# NextOne.net
KiCad netlist of a schematic drawn in EAGLE
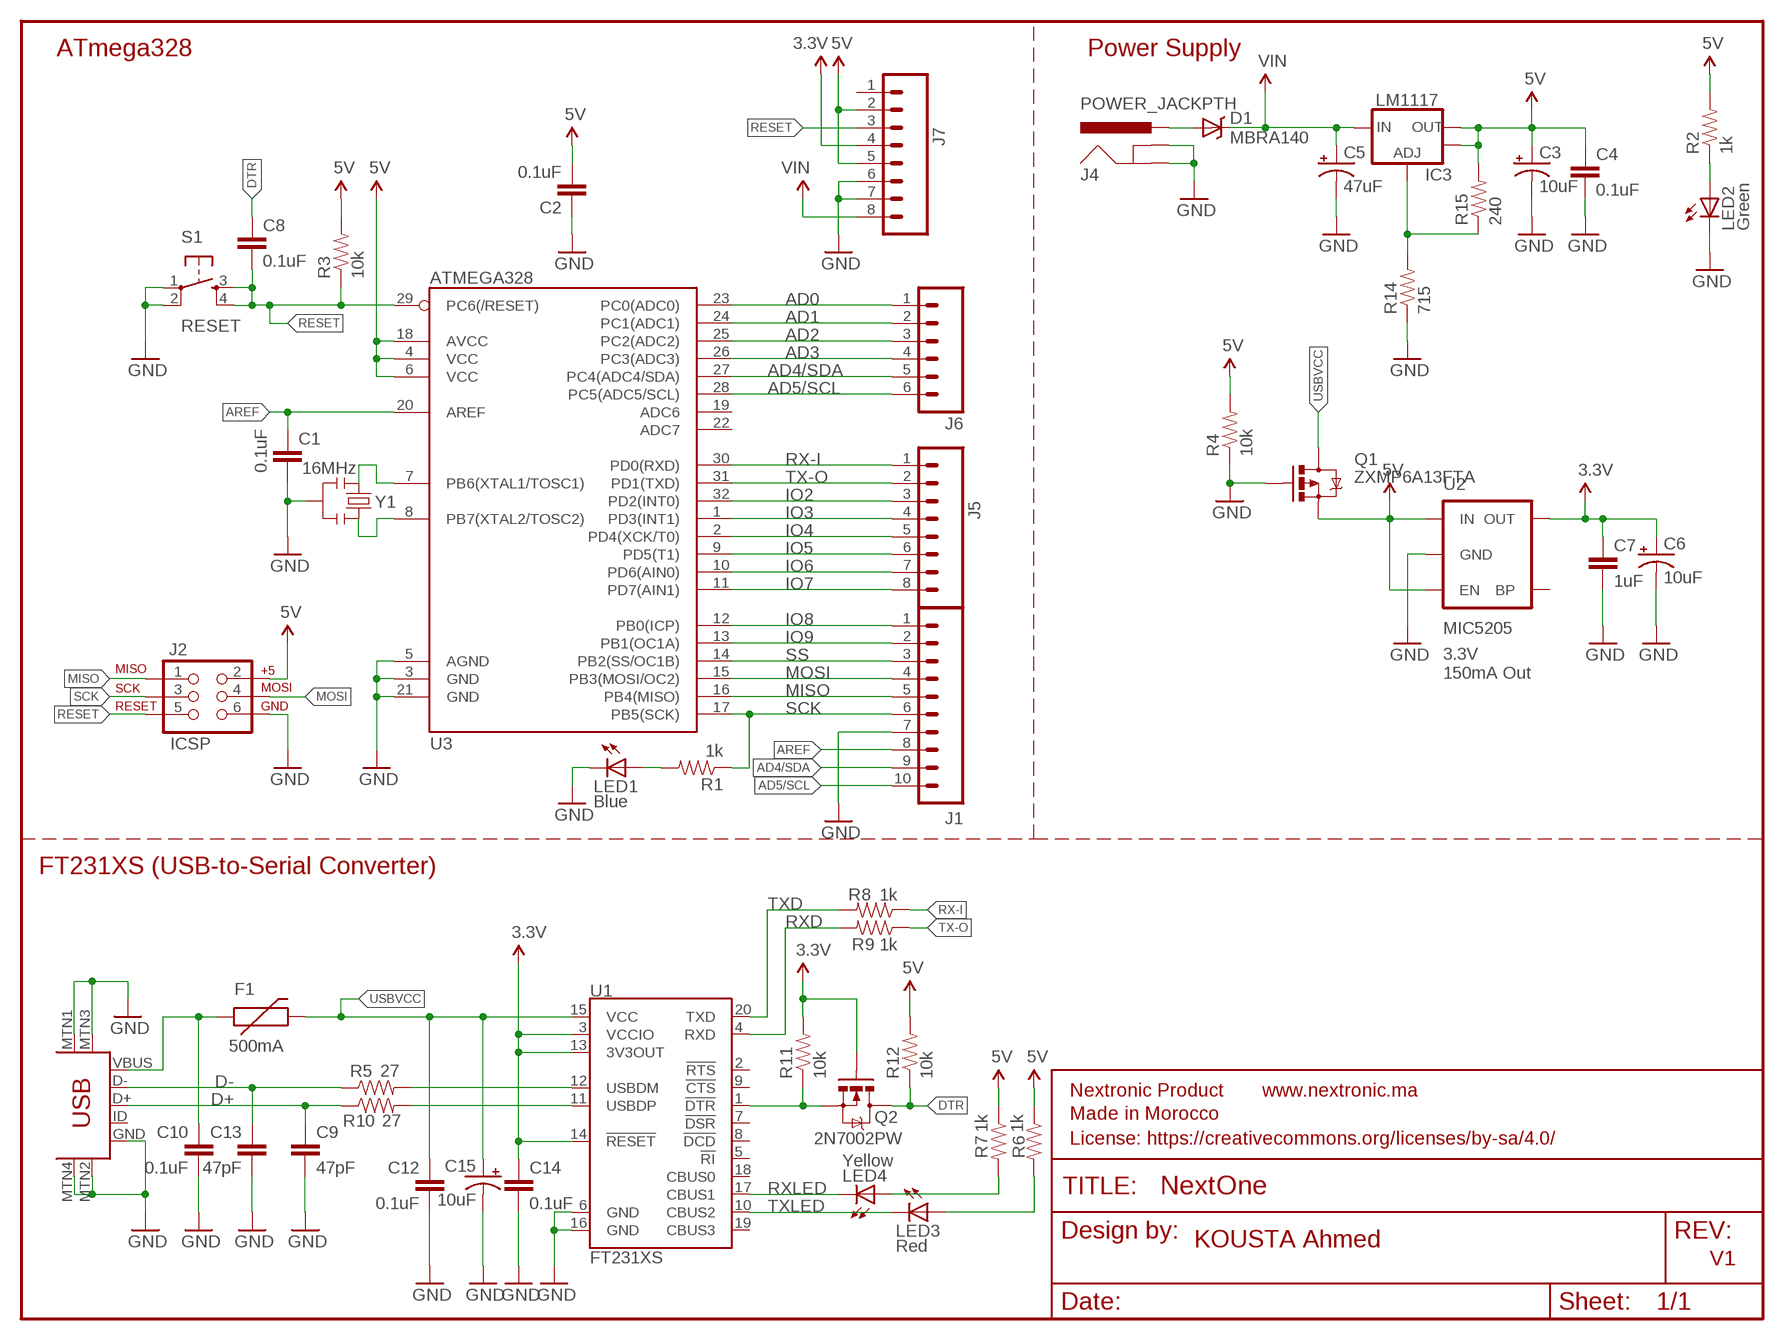
[diagram p0: schematic, sheet 1]

(export (version "E")
  (design (tool "Eeschema 10.0.6"))
  (components
    (comp (ref "C1")
      (value "0.1uF")
      (footprint "eagle-import:0603-CAP")
      (libsource (lib "eagle-import") (part "CAP0603-CAP"))
    )
    (comp (ref "C2")
      (value "0.1uF")
      (footprint "eagle-import:0603-CAP")
      (libsource (lib "eagle-import") (part "CAP0603-CAP"))
    )
    (comp (ref "C3")
      (value "10uF")
      (footprint "eagle-import:EIA3216")
      (libsource (lib "eagle-import") (part "CAP_POL1206"))
    )
    (comp (ref "C4")
      (value "0.1uF")
      (footprint "eagle-import:0603-CAP")
      (libsource (lib "eagle-import") (part "CAP0603-CAP"))
    )
    (comp (ref "C5")
      (value "47uF")
      (footprint "eagle-import:PANASONIC_D")
      (fields (field (name "MF") "PANASONIC ELECTRONIC COMPONENTS") (field (name "MPN") "EEE1CA470SP"))
      (libsource (lib "eagle-import") (part "CAP_POLD"))
    )
    (comp (ref "C6")
      (value "10uF")
      (footprint "eagle-import:EIA3216")
      (libsource (lib "eagle-import") (part "CAP_POL1206"))
    )
    (comp (ref "C7")
      (value "1uF")
      (footprint "eagle-import:0603-CAP")
      (fields (field (name "MF") "WALSIN") (field (name "MPN") "0805B104K500CT"))
      (libsource (lib "eagle-import") (part "CAP0603-CAP"))
    )
    (comp (ref "C8")
      (value "0.1uF")
      (footprint "eagle-import:0603-CAP")
      (libsource (lib "eagle-import") (part "CAP0603-CAP"))
    )
    (comp (ref "C9")
      (value "47pF")
      (footprint "eagle-import:0603-CAP")
      (fields (field (name "MF") "AVX") (field (name "MPN") "12061A470JAT2A"))
      (libsource (lib "eagle-import") (part "47PF-50V-5%(0603)"))
    )
    (comp (ref "C10")
      (value "0.1uF")
      (footprint "eagle-import:0603-CAP")
      (libsource (lib "eagle-import") (part "CAP0603-CAP"))
    )
    (comp (ref "C12")
      (value "0.1uF")
      (footprint "eagle-import:0603-CAP")
      (libsource (lib "eagle-import") (part "CAP0603-CAP"))
    )
    (comp (ref "C13")
      (value "47pF")
      (footprint "eagle-import:0603-CAP")
      (fields (field (name "MF") "AVX") (field (name "MPN") "12061A470JAT2A"))
      (libsource (lib "eagle-import") (part "47PF-50V-5%(0603)"))
    )
    (comp (ref "C14")
      (value "0.1uF")
      (footprint "eagle-import:0603-CAP")
      (libsource (lib "eagle-import") (part "CAP0603-CAP"))
    )
    (comp (ref "C15")
      (value "10uF")
      (footprint "eagle-import:EIA3216")
      (libsource (lib "eagle-import") (part "SparkFun-Capacitors_CAP_POL1206"))
    )
    (comp (ref "D1")
      (value "MBRA140")
      (footprint "eagle-import:SMA-DIODE")
      (fields (field (name "MF") "DIODES INC.") (field (name "MPN") "B140-13-F"))
      (libsource (lib "eagle-import") (part "DIODE-SCHOTTKY_"))
    )
    (comp (ref "F1")
      (value "500mA")
      (footprint "eagle-import:PTC-1206")
      (fields (field (name "MF") "FAIRCHILD SEMICONDUCTOR") (field (name "MPN") "1N3070TR"))
      (libsource (lib "eagle-import") (part "PTCSMD"))
    )
    (comp (ref "FRAME1")
      (value "FRAME-LETTER")
      (footprint "eagle-import:CREATIVE_COMMONS")
      (fields (field (name "OC_FARNELL") "unknown"))
      (libsource (lib "eagle-import") (part "FRAME-LETTER"))
    )
    (comp (ref "IC3")
      (value "LM1117")
      (footprint "eagle-import:SOT223-ALT1")
      (fields (field (name "MF") "STMICROELECTRONICS") (field (name "MPN") "LD1117S33TR"))
      (libsource (lib "eagle-import") (part "V_REG_LM1117ALT1"))
    )
    (comp (ref "J1")
      (value "M10SILK_FEMALE_PTH")
      (footprint "eagle-import:1X10")
      (libsource (lib "eagle-import") (part "M10SILK_FEMALE_PTH"))
    )
    (comp (ref "J2")
      (value "ICSP")
      (footprint "eagle-import:2X3")
      (libsource (lib "eagle-import") (part "AVR_SPI_PRG_6PTH"))
    )
    (comp (ref "J4")
      (value "POWER_JACKPTH")
      (footprint "eagle-import:POWER_JACK_PTH")
      (libsource (lib "eagle-import") (part "POWER_JACKPTH"))
    )
    (comp (ref "J5")
      (value "M08")
      (footprint "eagle-import:1X08_ROUND")
      (libsource (lib "eagle-import") (part "M08"))
    )
    (comp (ref "J6")
      (value "M06SILK_FEMALE_PTH")
      (footprint "eagle-import:1X06")
      (libsource (lib "eagle-import") (part "M06SILK_FEMALE_PTH"))
    )
    (comp (ref "J7")
      (value "M08")
      (footprint "eagle-import:1X08_ROUND")
      (libsource (lib "eagle-import") (part "M08"))
    )
    (comp (ref "LED1")
      (value "Blue")
      (footprint "eagle-import:LED-1206-NO_SILK")
      (libsource (lib "eagle-import") (part "LED1206-NS"))
    )
    (comp (ref "LED2")
      (value "Green")
      (footprint "eagle-import:LED-1206-NO_SILK")
      (libsource (lib "eagle-import") (part "LED1206-NS"))
    )
    (comp (ref "LED3")
      (value "Red")
      (footprint "eagle-import:LED-1206-NO_SILK")
      (libsource (lib "eagle-import") (part "LED1206-NS"))
    )
    (comp (ref "LED4")
      (value "Yellow")
      (footprint "eagle-import:LED-1206-NO_SILK")
      (libsource (lib "eagle-import") (part "LED1206-NS"))
    )
    (comp (ref "Q1")
      (value "ZXMP6A13FTA")
      (footprint "eagle-import:SOT23-3")
      (fields (field (name "MF") "DIODES INC."))
      (libsource (lib "eagle-import") (part "MOSFET-PCHANNELSMD"))
    )
    (comp (ref "Q2")
      (value "2N7002PW")
      (footprint "eagle-import:SOT323")
      (libsource (lib "eagle-import") (part "MOSFET-NCHANNEL2N7002PW"))
    )
    (comp (ref "R1")
      (value "1k")
      (footprint "eagle-import:0603-RES")
      (libsource (lib "eagle-import") (part "RESISTOR0603-RES"))
    )
    (comp (ref "R2")
      (value "1k")
      (footprint "eagle-import:0603-RES")
      (libsource (lib "eagle-import") (part "RESISTOR0603-RES"))
    )
    (comp (ref "R3")
      (value "10k")
      (footprint "eagle-import:0603-RES")
      (libsource (lib "eagle-import") (part "RESISTOR0603-RES"))
    )
    (comp (ref "R4")
      (value "10k")
      (footprint "eagle-import:0603-RES")
      (libsource (lib "eagle-import") (part "RESISTOR0603-RES"))
    )
    (comp (ref "R5")
      (value "27")
      (footprint "eagle-import:0603-RES")
      (libsource (lib "eagle-import") (part "SparkFun-Resistors_RESISTOR0603-RES"))
    )
    (comp (ref "R6")
      (value "1k")
      (footprint "eagle-import:0603-RES")
      (libsource (lib "eagle-import") (part "RESISTOR0603-RES"))
    )
    (comp (ref "R7")
      (value "1k")
      (footprint "eagle-import:0603-RES")
      (libsource (lib "eagle-import") (part "RESISTOR0603-RES"))
    )
    (comp (ref "R8")
      (value "1k")
      (footprint "eagle-import:0603-RES")
      (libsource (lib "eagle-import") (part "RESISTOR0603-RES"))
    )
    (comp (ref "R9")
      (value "1k")
      (footprint "eagle-import:0603-RES")
      (libsource (lib "eagle-import") (part "RESISTOR0603-RES"))
    )
    (comp (ref "R10")
      (value "27")
      (footprint "eagle-import:0603-RES")
      (libsource (lib "eagle-import") (part "SparkFun-Resistors_RESISTOR0603-RES"))
    )
    (comp (ref "R11")
      (value "10k")
      (footprint "eagle-import:0603-RES")
      (libsource (lib "eagle-import") (part "RESISTOR0603-RES"))
    )
    (comp (ref "R12")
      (value "10k")
      (footprint "eagle-import:0603-RES")
      (libsource (lib "eagle-import") (part "RESISTOR0603-RES"))
    )
    (comp (ref "R14")
      (value "715")
      (footprint "eagle-import:0603-RES")
      (libsource (lib "eagle-import") (part "RESISTOR0603-RES"))
    )
    (comp (ref "R15")
      (value "240")
      (footprint "eagle-import:0603-RES")
      (libsource (lib "eagle-import") (part "RESISTOR0603-RES"))
    )
    (comp (ref "S1")
      (value "RESET")
      (footprint "eagle-import:TACTILE_SWITCH_SMD")
      (libsource (lib "eagle-import") (part "TAC_SWITCHSMD"))
    )
    (comp (ref "U$13")
      (value "USB-MINIB-5PIN")
      (footprint "eagle-import:USB-MINIB")
      (fields (field (name "MF") "TE CONNECTIVITY / AMP") (field (name "MPN") "1734035-1."))
      (libsource (lib "eagle-import") (part "USB-MINIB-5PIN"))
    )
    (comp (ref "U1")
      (value "FT231XS")
      (footprint "eagle-import:SSOP20_L")
      (fields (field (name "MF") "FTDI"))
      (libsource (lib "eagle-import") (part "FT231XS"))
    )
    (comp (ref "U2")
      (value "MIC5205")
      (footprint "eagle-import:SOT23-5")
      (libsource (lib "eagle-import") (part "V_REG_LDOSMD"))
    )
    (comp (ref "U3")
      (value "ATMEGA328")
      (footprint "eagle-import:TQFP32-08")
      (fields (field (name "MF") "ATMEL") (field (name "MPN") "ATMEGA328P-AN"))
      (libsource (lib "eagle-import") (part "ATMEGA168"))
    )
    (comp (ref "Y1")
      (value "16MHz")
      (footprint "eagle-import:RESONATOR-SMD")
      (libsource (lib "eagle-import") (part "RESONATORSMD"))
    )
  )
  (nets
    (net (code "1") (name "/AD0") (class "Default")
      (node (ref "J6") (pin "1") (pinfunction "1_1") (pintype "passive"))
      (node (ref "U3") (pin "23") (pinfunction "PC0(ADC0)_23") (pintype "bidirectional"))
    )
    (net (code "2") (name "/AD1") (class "Default")
      (node (ref "J6") (pin "2") (pinfunction "2_2") (pintype "passive"))
      (node (ref "U3") (pin "24") (pinfunction "PC1(ADC1)_24") (pintype "bidirectional"))
    )
    (net (code "3") (name "/AD2") (class "Default")
      (node (ref "J6") (pin "3") (pinfunction "3_3") (pintype "passive"))
      (node (ref "U3") (pin "25") (pinfunction "PC2(ADC2)_25") (pintype "bidirectional"))
    )
    (net (code "4") (name "/AD3") (class "Default")
      (node (ref "J6") (pin "4") (pinfunction "4_4") (pintype "passive"))
      (node (ref "U3") (pin "26") (pinfunction "PC3(ADC3)_26") (pintype "bidirectional"))
    )
    (net (code "5") (name "/D+") (class "Default")
      (node (ref "C9") (pin "1") (pinfunction "1_1") (pintype "passive"))
      (node (ref "R10") (pin "1") (pinfunction "1_1") (pintype "passive"))
      (node (ref "U$13") (pin "D+") (pinfunction "D+_D+") (pintype "bidirectional"))
    )
    (net (code "6") (name "/D-") (class "Default")
      (node (ref "C13") (pin "1") (pinfunction "1_1") (pintype "passive"))
      (node (ref "R5") (pin "1") (pinfunction "1_1") (pintype "passive"))
      (node (ref "U$13") (pin "D-") (pinfunction "D-_D-") (pintype "bidirectional"))
    )
    (net (code "7") (name "/IO2") (class "Default")
      (node (ref "J5") (pin "3") (pinfunction "3_3") (pintype "passive"))
      (node (ref "U3") (pin "32") (pinfunction "PD2(INT0)_32") (pintype "bidirectional"))
    )
    (net (code "8") (name "/IO3") (class "Default")
      (node (ref "J5") (pin "4") (pinfunction "4_4") (pintype "passive"))
      (node (ref "U3") (pin "1") (pinfunction "PD3(INT1)_1") (pintype "bidirectional"))
    )
    (net (code "9") (name "/IO4") (class "Default")
      (node (ref "J5") (pin "5") (pinfunction "5_5") (pintype "passive"))
      (node (ref "U3") (pin "2") (pinfunction "PD4(XCK/T0)_2") (pintype "bidirectional"))
    )
    (net (code "10") (name "/IO5") (class "Default")
      (node (ref "J5") (pin "6") (pinfunction "6_6") (pintype "passive"))
      (node (ref "U3") (pin "9") (pinfunction "PD5(T1)_9") (pintype "bidirectional"))
    )
    (net (code "11") (name "/IO6") (class "Default")
      (node (ref "J5") (pin "7") (pinfunction "7_7") (pintype "passive"))
      (node (ref "U3") (pin "10") (pinfunction "PD6(AIN0)_10") (pintype "bidirectional"))
    )
    (net (code "12") (name "/IO7") (class "Default")
      (node (ref "J5") (pin "8") (pinfunction "8_8") (pintype "passive"))
      (node (ref "U3") (pin "11") (pinfunction "PD7(AIN1)_11") (pintype "bidirectional"))
    )
    (net (code "13") (name "/IO8") (class "Default")
      (node (ref "J1") (pin "1") (pinfunction "1_1") (pintype "passive"))
      (node (ref "U3") (pin "12") (pinfunction "PB0(ICP)_12") (pintype "bidirectional"))
    )
    (net (code "14") (name "/IO9") (class "Default")
      (node (ref "J1") (pin "2") (pinfunction "2_2") (pintype "passive"))
      (node (ref "U3") (pin "13") (pinfunction "PB1(OC1A)_13") (pintype "bidirectional"))
    )
    (net (code "15") (name "/RXD") (class "Default")
      (node (ref "R9") (pin "2") (pinfunction "2_2") (pintype "passive"))
      (node (ref "U1") (pin "4") (pinfunction "RXD_4") (pintype "bidirectional"))
    )
    (net (code "16") (name "/RXLED") (class "Default")
      (node (ref "LED4") (pin "C") (pinfunction "C_C") (pintype "passive"))
      (node (ref "U1") (pin "17") (pinfunction "CBUS1_17") (pintype "bidirectional"))
    )
    (net (code "17") (name "/SS") (class "Default")
      (node (ref "J1") (pin "3") (pinfunction "3_3") (pintype "passive"))
      (node (ref "U3") (pin "14") (pinfunction "PB2(SS/OC1B)_14") (pintype "bidirectional"))
    )
    (net (code "18") (name "/TXD") (class "Default")
      (node (ref "R8") (pin "2") (pinfunction "2_2") (pintype "passive"))
      (node (ref "U1") (pin "20") (pinfunction "TXD_20") (pintype "bidirectional"))
    )
    (net (code "19") (name "/TXLED") (class "Default")
      (node (ref "LED3") (pin "C") (pinfunction "C_C") (pintype "passive"))
      (node (ref "U1") (pin "10") (pinfunction "CBUS2_10") (pintype "bidirectional"))
    )
    (net (code "20") (name "3.3V") (class "Default")
      (node (ref "C14") (pin "1") (pinfunction "1_1") (pintype "passive"))
      (node (ref "C6") (pin "A") (pinfunction "+_A") (pintype "passive"))
      (node (ref "C7") (pin "1") (pinfunction "1_1") (pintype "passive"))
      (node (ref "J7") (pin "4") (pinfunction "4_4") (pintype "passive"))
      (node (ref "Q2") (pin "1") (pinfunction "G_1") (pintype "passive"))
      (node (ref "R11") (pin "2") (pinfunction "2_2") (pintype "passive"))
      (node (ref "U1") (pin "13") (pinfunction "3V3OUT_13") (pintype "bidirectional"))
      (node (ref "U1") (pin "14") (pinfunction "~{RESET}_14") (pintype "bidirectional"))
      (node (ref "U1") (pin "3") (pinfunction "VCCIO_3") (pintype "bidirectional"))
      (node (ref "U2") (pin "5") (pinfunction "OUT_5") (pintype "passive"))
    )
    (net (code "21") (name "5V") (class "Default")
      (node (ref "C2") (pin "2") (pinfunction "2_2") (pintype "passive"))
      (node (ref "C3") (pin "A") (pinfunction "+_A") (pintype "passive"))
      (node (ref "C4") (pin "1") (pinfunction "1_1") (pintype "passive"))
      (node (ref "IC3") (pin "2") (pinfunction "OUT_2") (pintype "output"))
      (node (ref "IC3") (pin "4") (pinfunction "OUT_4") (pintype "output"))
      (node (ref "J2") (pin "2") (pinfunction "2_2") (pintype "passive"))
      (node (ref "J7") (pin "2") (pinfunction "2_2") (pintype "passive"))
      (node (ref "J7") (pin "5") (pinfunction "5_5") (pintype "passive"))
      (node (ref "Q1") (pin "2") (pinfunction "S_2") (pintype "passive"))
      (node (ref "R12") (pin "2") (pinfunction "2_2") (pintype "passive"))
      (node (ref "R15") (pin "2") (pinfunction "2_2") (pintype "passive"))
      (node (ref "R2") (pin "2") (pinfunction "2_2") (pintype "passive"))
      (node (ref "R3") (pin "2") (pinfunction "2_2") (pintype "passive"))
      (node (ref "R4") (pin "2") (pinfunction "2_2") (pintype "passive"))
      (node (ref "R6") (pin "1") (pinfunction "1_1") (pintype "passive"))
      (node (ref "R7") (pin "1") (pinfunction "1_1") (pintype "passive"))
      (node (ref "U2") (pin "1") (pinfunction "IN_1") (pintype "input"))
      (node (ref "U2") (pin "3") (pinfunction "EN_3") (pintype "input"))
      (node (ref "U3") (pin "18") (pinfunction "AVCC_18") (pintype "bidirectional"))
      (node (ref "U3") (pin "4") (pinfunction "VCC_4") (pintype "bidirectional"))
      (node (ref "U3") (pin "6") (pinfunction "VCC_6") (pintype "bidirectional"))
    )
    (net (code "22") (name "AD4{slash}SDA") (class "Default")
      (node (ref "J1") (pin "9") (pinfunction "9_9") (pintype "passive"))
      (node (ref "J6") (pin "5") (pinfunction "5_5") (pintype "passive"))
      (node (ref "U3") (pin "27") (pinfunction "PC4(ADC4/SDA)_27") (pintype "bidirectional"))
    )
    (net (code "23") (name "AD5{slash}SCL") (class "Default")
      (node (ref "J1") (pin "10") (pinfunction "10_10") (pintype "passive"))
      (node (ref "J6") (pin "6") (pinfunction "6_6") (pintype "passive"))
      (node (ref "U3") (pin "28") (pinfunction "PC5(ADC5/SCL)_28") (pintype "bidirectional"))
    )
    (net (code "24") (name "AREF") (class "Default")
      (node (ref "C1") (pin "1") (pinfunction "1_1") (pintype "passive"))
      (node (ref "J1") (pin "8") (pinfunction "8_8") (pintype "passive"))
      (node (ref "U3") (pin "20") (pinfunction "AREF_20") (pintype "bidirectional"))
    )
    (net (code "25") (name "DTR") (class "Default")
      (node (ref "C8") (pin "1") (pinfunction "1_1") (pintype "passive"))
      (node (ref "Q2") (pin "3") (pinfunction "D_3") (pintype "passive"))
      (node (ref "R12") (pin "1") (pinfunction "1_1") (pintype "passive"))
    )
    (net (code "26") (name "GND") (class "Default")
      (node (ref "C1") (pin "2") (pinfunction "2_2") (pintype "passive"))
      (node (ref "C10") (pin "2") (pinfunction "2_2") (pintype "passive"))
      (node (ref "C12") (pin "2") (pinfunction "2_2") (pintype "passive"))
      (node (ref "C13") (pin "2") (pinfunction "2_2") (pintype "passive"))
      (node (ref "C14") (pin "2") (pinfunction "2_2") (pintype "passive"))
      (node (ref "C15") (pin "C") (pinfunction "-_C") (pintype "passive"))
      (node (ref "C2") (pin "1") (pinfunction "1_1") (pintype "passive"))
      (node (ref "C3") (pin "C") (pinfunction "-_C") (pintype "passive"))
      (node (ref "C4") (pin "2") (pinfunction "2_2") (pintype "passive"))
      (node (ref "C5") (pin "-") (pinfunction "-_-") (pintype "passive"))
      (node (ref "C6") (pin "C") (pinfunction "-_C") (pintype "passive"))
      (node (ref "C7") (pin "2") (pinfunction "2_2") (pintype "passive"))
      (node (ref "C9") (pin "2") (pinfunction "2_2") (pintype "passive"))
      (node (ref "J1") (pin "7") (pinfunction "7_7") (pintype "passive"))
      (node (ref "J2") (pin "6") (pinfunction "6_6") (pintype "passive"))
      (node (ref "J4") (pin "GND") (pinfunction "GND_GND") (pintype "bidirectional"))
      (node (ref "J4") (pin "GNDBREAK") (pinfunction "GNDBREAK_GNDBREAK") (pintype "bidirectional"))
      (node (ref "J7") (pin "6") (pinfunction "6_6") (pintype "passive"))
      (node (ref "J7") (pin "7") (pinfunction "7_7") (pintype "passive"))
      (node (ref "LED1") (pin "C") (pinfunction "C_C") (pintype "passive"))
      (node (ref "LED2") (pin "C") (pinfunction "C_C") (pintype "passive"))
      (node (ref "Q1") (pin "1") (pinfunction "G_1") (pintype "passive"))
      (node (ref "R14") (pin "1") (pinfunction "1_1") (pintype "passive"))
      (node (ref "R4") (pin "1") (pinfunction "1_1") (pintype "passive"))
      (node (ref "S1") (pin "1") (pinfunction "1_1") (pintype "passive"))
      (node (ref "S1") (pin "2") (pinfunction "2_2") (pintype "passive"))
      (node (ref "U$13") (pin "GND") (pinfunction "GND_GND") (pintype "bidirectional"))
      (node (ref "U$13") (pin "MTN1") (pinfunction "MTN2_MTN1") (pintype "bidirectional"))
      (node (ref "U$13") (pin "MTN2") (pinfunction "MTN3_MTN2") (pintype "bidirectional"))
      (node (ref "U$13") (pin "MTN3") (pinfunction "MTN1_MTN3") (pintype "bidirectional"))
      (node (ref "U$13") (pin "MTN4") (pinfunction "MTN4_MTN4") (pintype "bidirectional"))
      (node (ref "U1") (pin "16") (pinfunction "GND_16") (pintype "bidirectional"))
      (node (ref "U1") (pin "6") (pinfunction "GND_6") (pintype "bidirectional"))
      (node (ref "U2") (pin "2") (pinfunction "GND_2") (pintype "input"))
      (node (ref "U3") (pin "21") (pinfunction "GND_21") (pintype "bidirectional"))
      (node (ref "U3") (pin "3") (pinfunction "GND_3") (pintype "bidirectional"))
      (node (ref "U3") (pin "5") (pinfunction "AGND_5") (pintype "bidirectional"))
      (node (ref "Y1") (pin "2") (pinfunction "2_2") (pintype "passive"))
    )
    (net (code "27") (name "MISO") (class "Default")
      (node (ref "J1") (pin "5") (pinfunction "5_5") (pintype "passive"))
      (node (ref "J2") (pin "1") (pinfunction "1_1") (pintype "passive"))
      (node (ref "U3") (pin "16") (pinfunction "PB4(MISO)_16") (pintype "bidirectional"))
    )
    (net (code "28") (name "MOSI") (class "Default")
      (node (ref "J1") (pin "4") (pinfunction "4_4") (pintype "passive"))
      (node (ref "J2") (pin "4") (pinfunction "4_4") (pintype "passive"))
      (node (ref "U3") (pin "15") (pinfunction "PB3(MOSI/OC2)_15") (pintype "bidirectional"))
    )
    (net (code "29") (name "Net-(C10-Pad1)") (class "Default")
      (node (ref "C10") (pin "1") (pinfunction "1_1") (pintype "passive"))
      (node (ref "F1") (pin "1") (pinfunction "1_1") (pintype "bidirectional"))
      (node (ref "U$13") (pin "VBUS") (pinfunction "VBUS_VBUS") (pintype "bidirectional"))
    )
    (net (code "30") (name "Net-(D1-PadA)") (class "Default")
      (node (ref "D1") (pin "A") (pinfunction "A_A") (pintype "passive"))
      (node (ref "J4") (pin "PWR") (pinfunction "PWR_PWR") (pintype "bidirectional"))
    )
    (net (code "31") (name "Net-(IC3-ADJ)") (class "Default")
      (node (ref "IC3") (pin "1") (pinfunction "ADJ_1") (pintype "input"))
      (node (ref "R14") (pin "2") (pinfunction "2_2") (pintype "passive"))
      (node (ref "R15") (pin "1") (pinfunction "1_1") (pintype "passive"))
    )
    (net (code "32") (name "Net-(LED1-PadA)") (class "Default")
      (node (ref "LED1") (pin "A") (pinfunction "A_A") (pintype "passive"))
      (node (ref "R1") (pin "2") (pinfunction "2_2") (pintype "passive"))
    )
    (net (code "33") (name "Net-(LED2-PadA)") (class "Default")
      (node (ref "LED2") (pin "A") (pinfunction "A_A") (pintype "passive"))
      (node (ref "R2") (pin "1") (pinfunction "1_1") (pintype "passive"))
    )
    (net (code "34") (name "Net-(LED3-PadA)") (class "Default")
      (node (ref "LED3") (pin "A") (pinfunction "A_A") (pintype "passive"))
      (node (ref "R6") (pin "2") (pinfunction "2_2") (pintype "passive"))
    )
    (net (code "35") (name "Net-(LED4-PadA)") (class "Default")
      (node (ref "LED4") (pin "A") (pinfunction "A_A") (pintype "passive"))
      (node (ref "R7") (pin "2") (pinfunction "2_2") (pintype "passive"))
    )
    (net (code "36") (name "Net-(Q2-S)") (class "Default")
      (node (ref "Q2") (pin "2") (pinfunction "S_2") (pintype "passive"))
      (node (ref "R11") (pin "1") (pinfunction "1_1") (pintype "passive"))
      (node (ref "U1") (pin "1") (pinfunction "~{DTR}_1") (pintype "bidirectional"))
    )
    (net (code "37") (name "Net-(U1-USBDM)") (class "Default")
      (node (ref "R5") (pin "2") (pinfunction "2_2") (pintype "passive"))
      (node (ref "U1") (pin "12") (pinfunction "USBDM_12") (pintype "bidirectional"))
    )
    (net (code "38") (name "Net-(U1-USBDP)") (class "Default")
      (node (ref "R10") (pin "2") (pinfunction "2_2") (pintype "passive"))
      (node (ref "U1") (pin "11") (pinfunction "USBDP_11") (pintype "bidirectional"))
    )
    (net (code "39") (name "Net-(U3-PB6(XTAL1{slash}TOSC1))") (class "Default")
      (node (ref "U3") (pin "7") (pinfunction "PB6(XTAL1/TOSC1)_7") (pintype "bidirectional"))
      (node (ref "Y1") (pin "1") (pinfunction "1_1") (pintype "passive"))
    )
    (net (code "40") (name "Net-(U3-PB7(XTAL2{slash}TOSC2))") (class "Default")
      (node (ref "U3") (pin "8") (pinfunction "PB7(XTAL2/TOSC2)_8") (pintype "bidirectional"))
      (node (ref "Y1") (pin "3") (pinfunction "3_3") (pintype "passive"))
    )
    (net (code "41") (name "RESET") (class "Default")
      (node (ref "C8") (pin "2") (pinfunction "2_2") (pintype "passive"))
      (node (ref "J2") (pin "5") (pinfunction "5_5") (pintype "passive"))
      (node (ref "J7") (pin "3") (pinfunction "3_3") (pintype "passive"))
      (node (ref "R3") (pin "1") (pinfunction "1_1") (pintype "passive"))
      (node (ref "S1") (pin "3") (pinfunction "3_3") (pintype "passive"))
      (node (ref "S1") (pin "4") (pinfunction "4_4") (pintype "passive"))
      (node (ref "U3") (pin "29") (pinfunction "PC6(/RESET)_29") (pintype "bidirectional"))
    )
    (net (code "42") (name "RX-I") (class "Default")
      (node (ref "J5") (pin "1") (pinfunction "1_1") (pintype "passive"))
      (node (ref "R8") (pin "1") (pinfunction "1_1") (pintype "passive"))
      (node (ref "U3") (pin "30") (pinfunction "PD0(RXD)_30") (pintype "bidirectional"))
    )
    (net (code "43") (name "SCK") (class "Default")
      (node (ref "J1") (pin "6") (pinfunction "6_6") (pintype "passive"))
      (node (ref "J2") (pin "3") (pinfunction "3_3") (pintype "passive"))
      (node (ref "R1") (pin "1") (pinfunction "1_1") (pintype "passive"))
      (node (ref "U3") (pin "17") (pinfunction "PB5(SCK)_17") (pintype "bidirectional"))
    )
    (net (code "44") (name "TX-O") (class "Default")
      (node (ref "J5") (pin "2") (pinfunction "2_2") (pintype "passive"))
      (node (ref "R9") (pin "1") (pinfunction "1_1") (pintype "passive"))
      (node (ref "U3") (pin "31") (pinfunction "PD1(TXD)_31") (pintype "bidirectional"))
    )
    (net (code "45") (name "USBVCC") (class "Default")
      (node (ref "C12") (pin "1") (pinfunction "1_1") (pintype "passive"))
      (node (ref "C15") (pin "A") (pinfunction "+_A") (pintype "passive"))
      (node (ref "F1") (pin "2") (pinfunction "2_2") (pintype "bidirectional"))
      (node (ref "Q1") (pin "3") (pinfunction "D_3") (pintype "passive"))
      (node (ref "U1") (pin "15") (pinfunction "VCC_15") (pintype "bidirectional"))
    )
    (net (code "46") (name "VIN") (class "Default")
      (node (ref "C5") (pin "+") (pinfunction "+_+") (pintype "passive"))
      (node (ref "D1") (pin "C") (pinfunction "C_C") (pintype "passive"))
      (node (ref "IC3") (pin "3") (pinfunction "IN_3") (pintype "input"))
      (node (ref "J7") (pin "8") (pinfunction "8_8") (pintype "passive"))
    )
    (net (code "47") (name "unconnected-(J7-Pad1)") (class "Default")
      (node (ref "J7") (pin "1") (pinfunction "1_1") (pintype "passive"))
    )
    (net (code "48") (name "unconnected-(U$13-PadID)") (class "Default")
      (node (ref "U$13") (pin "ID") (pinfunction "ID_ID") (pintype "bidirectional"))
    )
    (net (code "49") (name "unconnected-(U1-CBUS0-Pad18)") (class "Default")
      (node (ref "U1") (pin "18") (pinfunction "CBUS0_18") (pintype "bidirectional"))
    )
    (net (code "50") (name "unconnected-(U1-CBUS3-Pad19)") (class "Default")
      (node (ref "U1") (pin "19") (pinfunction "CBUS3_19") (pintype "bidirectional"))
    )
    (net (code "51") (name "unconnected-(U1-~{CTS}-Pad9)") (class "Default")
      (node (ref "U1") (pin "9") (pinfunction "~{CTS}_9") (pintype "bidirectional"))
    )
    (net (code "52") (name "unconnected-(U1-~{DCD}-Pad8)") (class "Default")
      (node (ref "U1") (pin "8") (pinfunction "~{DCD}_8") (pintype "bidirectional"))
    )
    (net (code "53") (name "unconnected-(U1-~{DSR}-Pad7)") (class "Default")
      (node (ref "U1") (pin "7") (pinfunction "~{DSR}_7") (pintype "bidirectional"))
    )
    (net (code "54") (name "unconnected-(U1-~{RI}-Pad5)") (class "Default")
      (node (ref "U1") (pin "5") (pinfunction "~{RI}_5") (pintype "bidirectional"))
    )
    (net (code "55") (name "unconnected-(U1-~{RTS}-Pad2)") (class "Default")
      (node (ref "U1") (pin "2") (pinfunction "~{RTS}_2") (pintype "bidirectional"))
    )
    (net (code "56") (name "unconnected-(U2-BP-Pad4)") (class "Default")
      (node (ref "U2") (pin "4") (pinfunction "BP_4") (pintype "input"))
    )
    (net (code "57") (name "unconnected-(U3-ADC6-Pad19)") (class "Default")
      (node (ref "U3") (pin "19") (pinfunction "ADC6_19") (pintype "bidirectional"))
    )
    (net (code "58") (name "unconnected-(U3-ADC7-Pad22)") (class "Default")
      (node (ref "U3") (pin "22") (pinfunction "ADC7_22") (pintype "bidirectional"))
    )
  )
)
